# TSAL.net
KiCad netlist of a schematic drawn in EAGLE
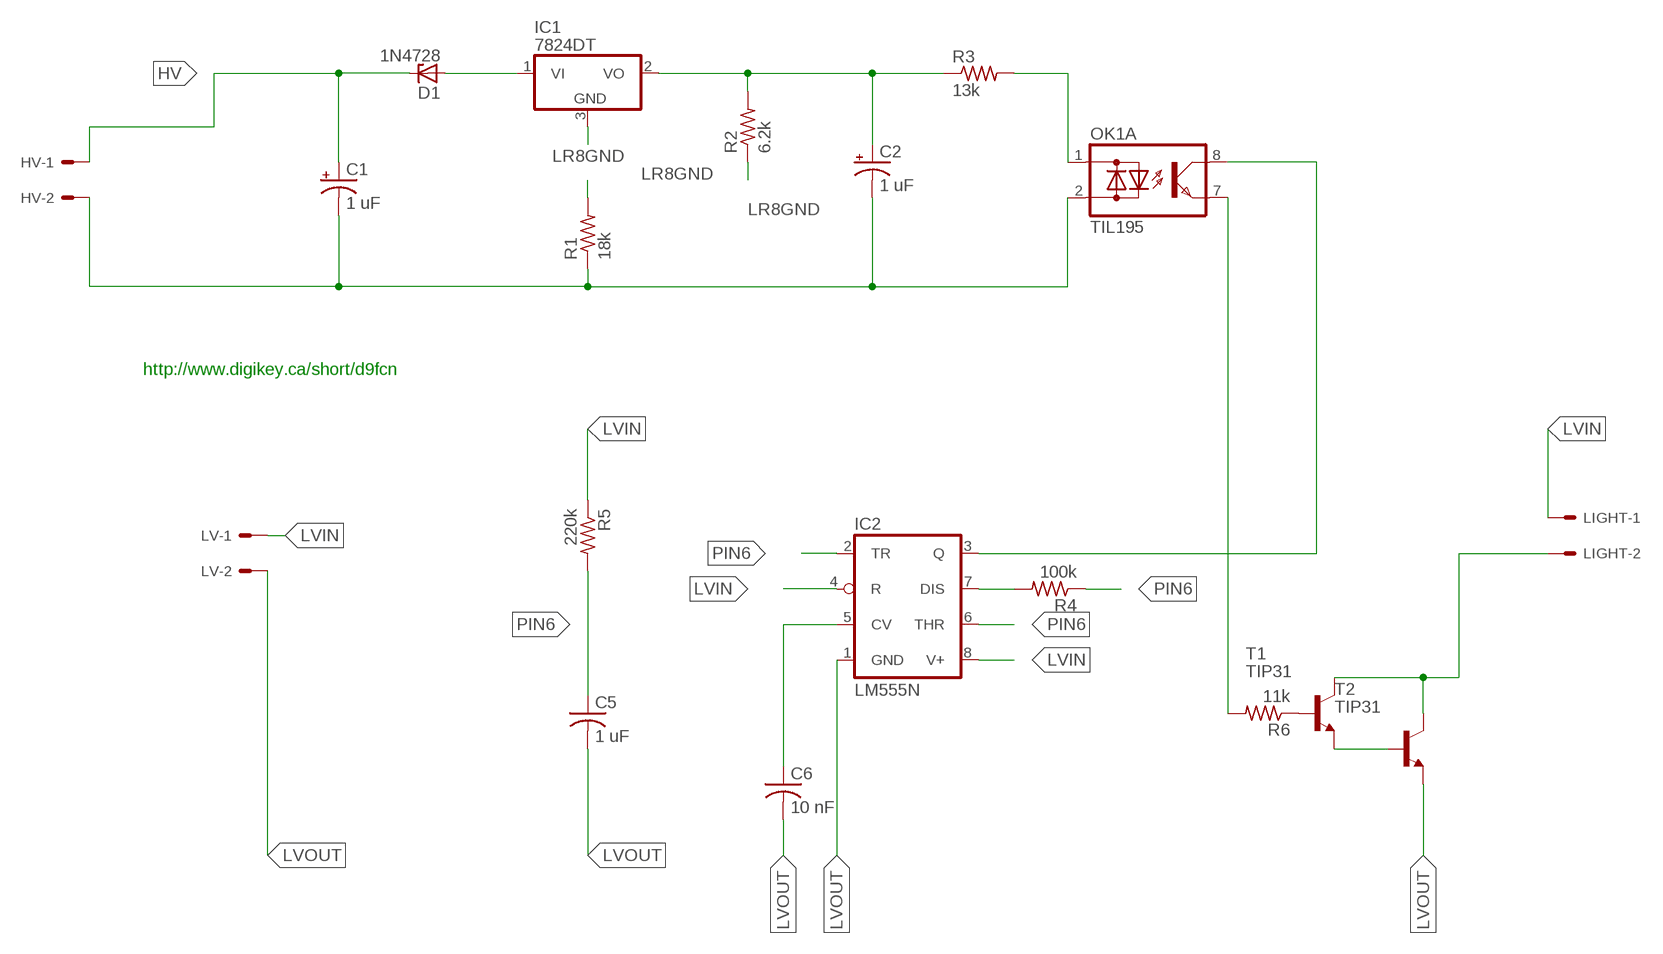
[diagram p0: schematic, sheet 1]

(export (version "E")
  (design (tool "Eeschema 10.0.6"))
  (components
    (comp (ref "C1")
      (value "1 uF")
      (footprint "eagle-import:E2,5-7")
      (libsource (lib "eagle-import") (part "CPOL-USE2.5-7"))
    )
    (comp (ref "C2")
      (value "1 uF")
      (footprint "eagle-import:E2,5-7")
      (libsource (lib "eagle-import") (part "CPOL-USE2.5-7"))
    )
    (comp (ref "C5")
      (value "1 uF")
      (footprint "eagle-import:C050-035X075")
      (libsource (lib "eagle-import") (part "C-US050-035X075"))
    )
    (comp (ref "C6")
      (value "10 nF")
      (footprint "eagle-import:C025-025X050")
      (libsource (lib "eagle-import") (part "C-US025-025X050"))
    )
    (comp (ref "D1")
      (value "1N4728")
      (footprint "eagle-import:DO41Z10")
      (libsource (lib "eagle-import") (part "1N4728"))
    )
    (comp (ref "HV")
      (value "KK-156-2")
      (footprint "eagle-import:KK-156-2")
      (libsource (lib "eagle-import") (part "KK-156-2"))
    )
    (comp (ref "IC1")
      (value "7824DT")
      (footprint "eagle-import:TO252")
      (libsource (lib "eagle-import") (part "78DT24"))
    )
    (comp (ref "IC2")
      (value "LM555N")
      (footprint "eagle-import:DIL08-ROUND")
      (libsource (lib "eagle-import") (part "555NLM"))
    )
    (comp (ref "LIGHT")
      (value "KK-156-2")
      (footprint "eagle-import:KK-156-2")
      (libsource (lib "eagle-import") (part "KK-156-2"))
    )
    (comp (ref "LV")
      (value "KK-156-2")
      (footprint "eagle-import:KK-156-2")
      (libsource (lib "eagle-import") (part "KK-156-2"))
    )
    (comp (ref "OK1")
      (value "TIL195")
      (footprint "eagle-import:DIL08")
      (libsource (lib "eagle-import") (part "TIL195"))
    )
    (comp (ref "R1")
      (value "18k")
      (footprint "eagle-import:0617_22")
      (libsource (lib "eagle-import") (part "R-US_0617/22"))
    )
    (comp (ref "R2")
      (value "6.2k")
      (footprint "eagle-import:0617_22")
      (libsource (lib "eagle-import") (part "R-US_0617/22"))
    )
    (comp (ref "R3")
      (value "13k")
      (footprint "eagle-import:0617_17")
      (libsource (lib "eagle-import") (part "R-US_0617/17"))
    )
    (comp (ref "R4")
      (value "100k")
      (footprint "eagle-import:0207_7")
      (libsource (lib "eagle-import") (part "R-US_0207/7"))
    )
    (comp (ref "R5")
      (value "220k")
      (footprint "eagle-import:0207_7")
      (libsource (lib "eagle-import") (part "R-US_0207/7"))
    )
    (comp (ref "R6")
      (value "11k")
      (footprint "eagle-import:0411_12")
      (libsource (lib "eagle-import") (part "R-US_0411/12"))
    )
    (comp (ref "T1")
      (value "TIP31")
      (footprint "eagle-import:TO220")
      (libsource (lib "eagle-import") (part "TIP31"))
    )
    (comp (ref "T2")
      (value "TIP31")
      (footprint "eagle-import:TO220")
      (libsource (lib "eagle-import") (part "TIP31"))
    )
  )
  (nets
    (net (code "1") (name "/LR8GND") (class "Default")
      (node (ref "IC1") (pin "3") (pinfunction "GND_3") (pintype "passive"))
      (node (ref "R1") (pin "2") (pinfunction "2_2") (pintype "passive"))
      (node (ref "R2") (pin "1") (pinfunction "1_1") (pintype "passive"))
    )
    (net (code "2") (name "HV") (class "Default")
      (node (ref "C1") (pin "+") (pinfunction "+_+") (pintype "passive"))
      (node (ref "D1") (pin "C") (pinfunction "C_C") (pintype "passive"))
      (node (ref "HV") (pin "1") (pinfunction "S_1") (pintype "passive"))
    )
    (net (code "3") (name "LVIN") (class "Default")
      (node (ref "IC2") (pin "4") (pinfunction "R_4") (pintype "input"))
      (node (ref "IC2") (pin "8") (pinfunction "V+_8") (pintype "power_in"))
      (node (ref "LIGHT") (pin "1") (pinfunction "S_1") (pintype "passive"))
      (node (ref "LV") (pin "1") (pinfunction "S_1") (pintype "passive"))
      (node (ref "R5") (pin "1") (pinfunction "1_1") (pintype "passive"))
    )
    (net (code "4") (name "LVOUT") (class "Default")
      (node (ref "C5") (pin "2") (pinfunction "2_2") (pintype "passive"))
      (node (ref "C6") (pin "2") (pinfunction "2_2") (pintype "passive"))
      (node (ref "IC2") (pin "1") (pinfunction "GND_1") (pintype "power_in"))
      (node (ref "LV") (pin "2") (pinfunction "S_2") (pintype "passive"))
      (node (ref "T2") (pin "3") (pinfunction "E_3") (pintype "passive"))
    )
    (net (code "5") (name "Net-(HVB-S)") (class "Default")
      (node (ref "C1") (pin "-") (pinfunction "-_-") (pintype "passive"))
      (node (ref "C2") (pin "-") (pinfunction "-_-") (pintype "passive"))
      (node (ref "HV") (pin "2") (pinfunction "S_2") (pintype "passive"))
      (node (ref "OK1") (pin "2") (pinfunction "AC2_2") (pintype "passive"))
      (node (ref "R1") (pin "1") (pinfunction "1_1") (pintype "passive"))
    )
    (net (code "6") (name "Net-(IC1-VI)") (class "Default")
      (node (ref "D1") (pin "A") (pinfunction "A_A") (pintype "passive"))
      (node (ref "IC1") (pin "1") (pinfunction "VI_1") (pintype "input"))
    )
    (net (code "7") (name "Net-(IC1-VO)") (class "Default")
      (node (ref "C2") (pin "+") (pinfunction "+_+") (pintype "passive"))
      (node (ref "IC1") (pin "2") (pinfunction "VO_2") (pintype "passive"))
      (node (ref "R2") (pin "2") (pinfunction "2_2") (pintype "passive"))
      (node (ref "R3") (pin "1") (pinfunction "1_1") (pintype "passive"))
    )
    (net (code "8") (name "Net-(IC2-CV)") (class "Default")
      (node (ref "C6") (pin "1") (pinfunction "1_1") (pintype "passive"))
      (node (ref "IC2") (pin "5") (pinfunction "CV_5") (pintype "input"))
    )
    (net (code "9") (name "Net-(IC2-DIS)") (class "Default")
      (node (ref "IC2") (pin "7") (pinfunction "DIS_7") (pintype "input"))
      (node (ref "R4") (pin "2") (pinfunction "2_2") (pintype "passive"))
    )
    (net (code "10") (name "Net-(IC2-Q)") (class "Default")
      (node (ref "IC2") (pin "3") (pinfunction "Q_3") (pintype "output"))
      (node (ref "OK1") (pin "8") (pinfunction "C_8") (pintype "passive"))
    )
    (net (code "11") (name "Net-(LIGHTB-S)") (class "Default")
      (node (ref "LIGHT") (pin "2") (pinfunction "S_2") (pintype "passive"))
      (node (ref "T1") (pin "2") (pinfunction "C_2") (pintype "passive"))
      (node (ref "T2") (pin "2") (pinfunction "C_2") (pintype "passive"))
    )
    (net (code "12") (name "Net-(OK1A-AC1)") (class "Default")
      (node (ref "OK1") (pin "1") (pinfunction "AC1_1") (pintype "passive"))
      (node (ref "R3") (pin "2") (pinfunction "2_2") (pintype "passive"))
    )
    (net (code "13") (name "Net-(OK1A-E)") (class "Default")
      (node (ref "OK1") (pin "7") (pinfunction "E_7") (pintype "passive"))
      (node (ref "R6") (pin "2") (pinfunction "2_2") (pintype "passive"))
    )
    (net (code "14") (name "Net-(T1-B)") (class "Default")
      (node (ref "R6") (pin "1") (pinfunction "1_1") (pintype "passive"))
      (node (ref "T1") (pin "1") (pinfunction "B_1") (pintype "passive"))
    )
    (net (code "15") (name "Net-(T1-E)") (class "Default")
      (node (ref "T1") (pin "3") (pinfunction "E_3") (pintype "passive"))
      (node (ref "T2") (pin "1") (pinfunction "B_1") (pintype "passive"))
    )
    (net (code "16") (name "PIN6") (class "Default")
      (node (ref "C5") (pin "1") (pinfunction "1_1") (pintype "passive"))
      (node (ref "IC2") (pin "2") (pinfunction "TR_2") (pintype "input"))
      (node (ref "IC2") (pin "6") (pinfunction "THR_6") (pintype "input"))
      (node (ref "R4") (pin "1") (pinfunction "1_1") (pintype "passive"))
      (node (ref "R5") (pin "2") (pinfunction "2_2") (pintype "passive"))
    )
  )
)
